# Rocketometer9DS1_2.net
KiCad netlist of a schematic drawn in EAGLE
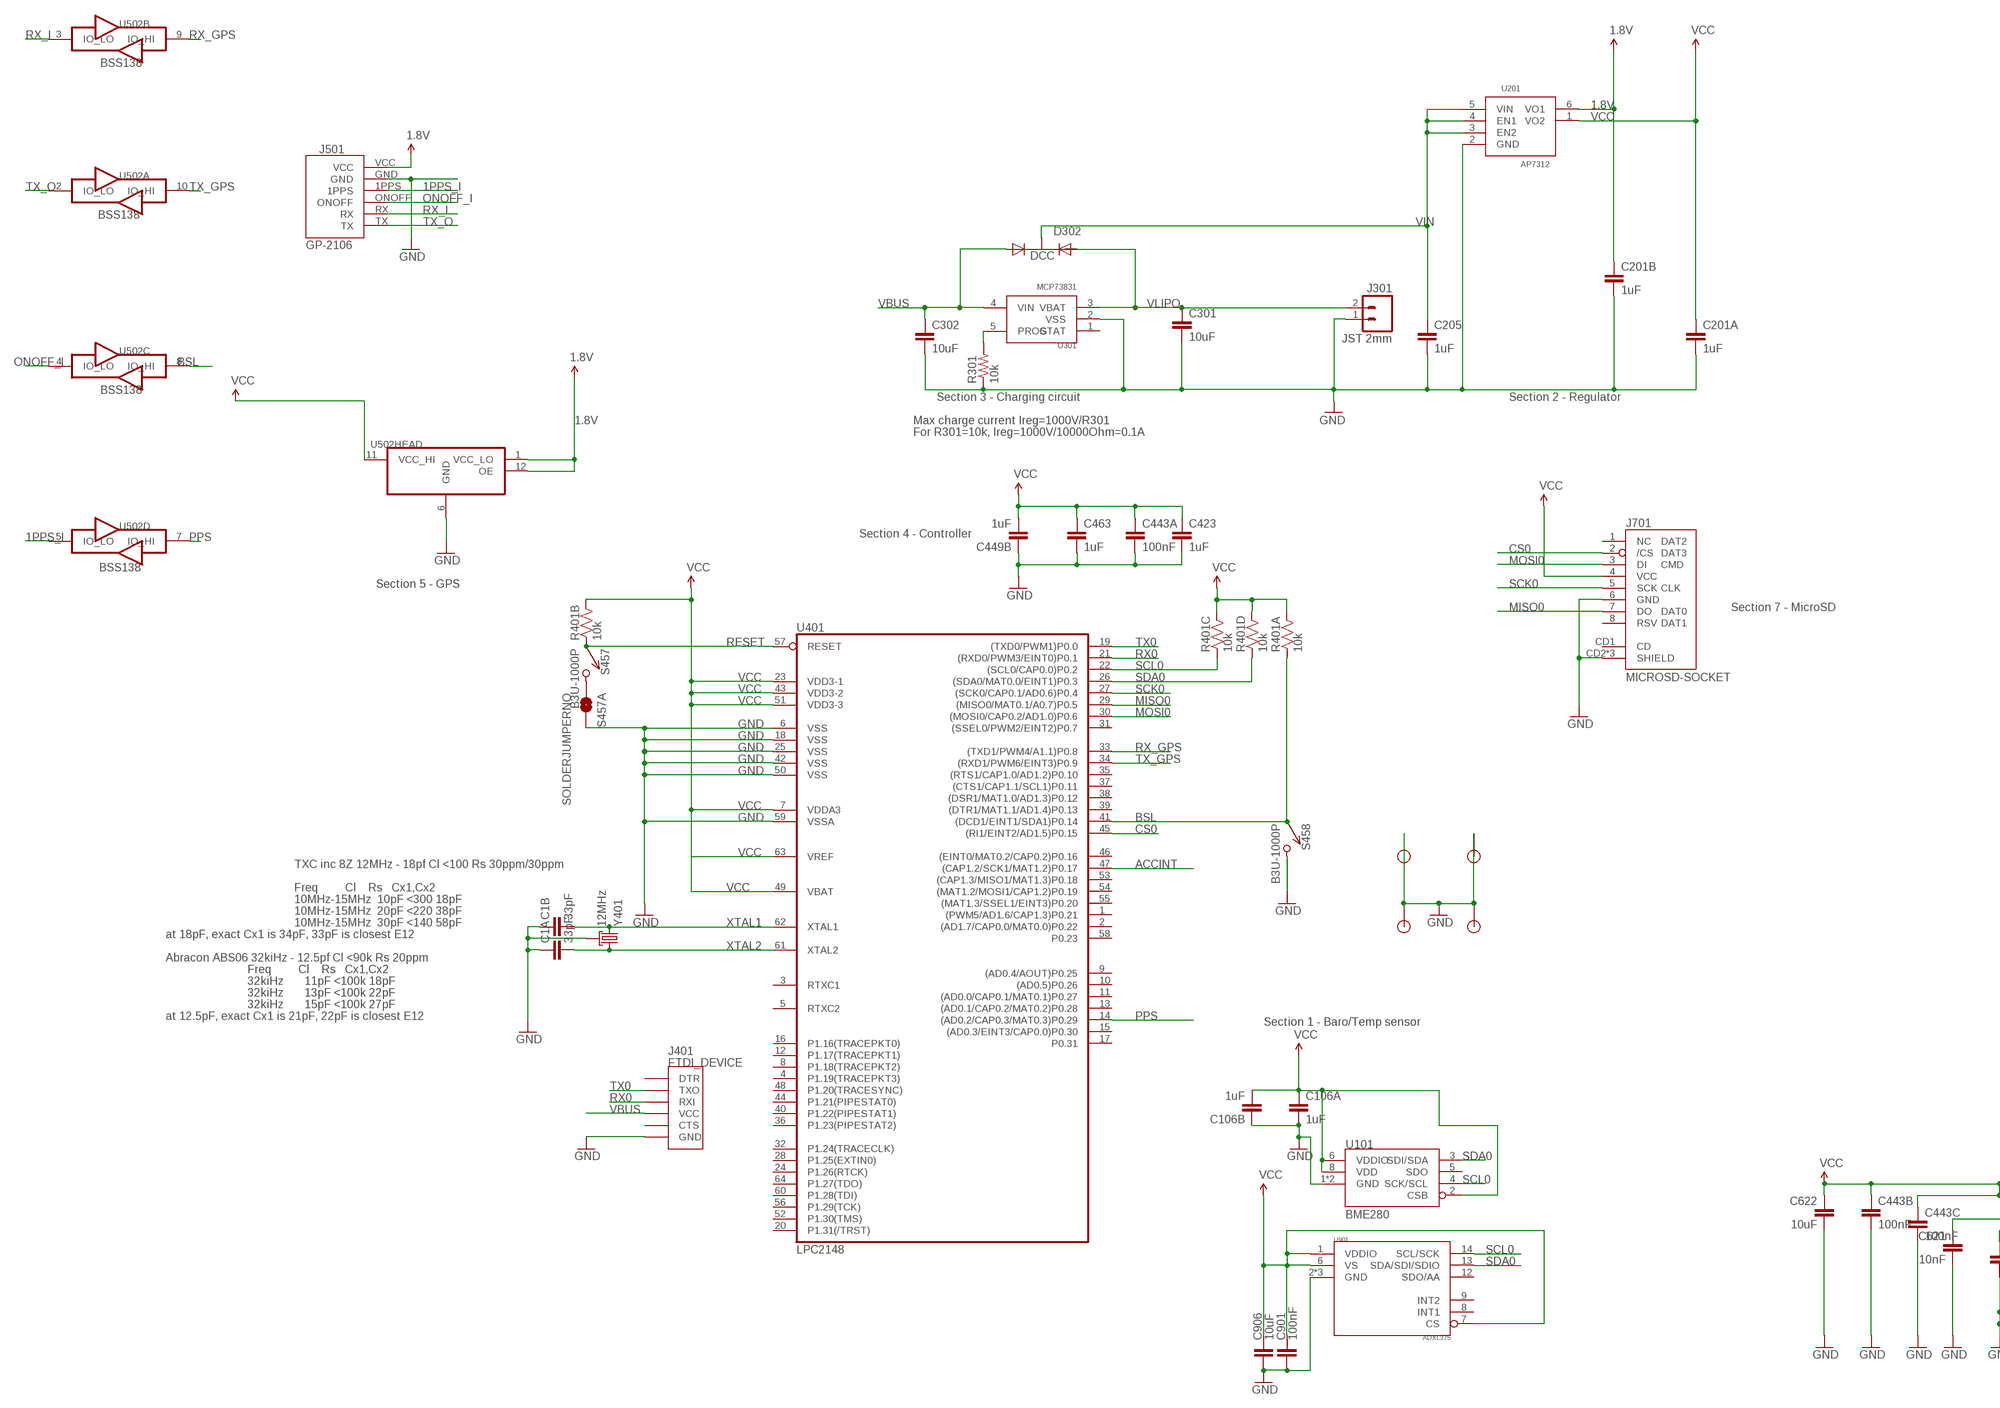
[diagram p0: schematic, sheet 1, part 1 of 2]
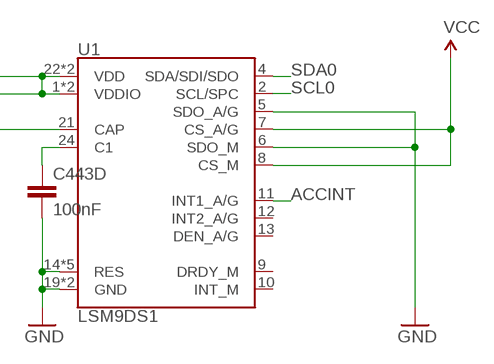
[diagram p1: schematic, sheet 1, part 2 of 2]

(export (version "E")
  (design (tool "Eeschema 10.0.6"))
  (components
    (comp (ref "C1")
      (value "33pF")
      (footprint "eagle-import:CKCM25")
      (libsource (lib "eagle-import") (part "CKCM25"))
    )
    (comp (ref "C106")
      (value "1uF")
      (footprint "eagle-import:CKCM25")
      (libsource (lib "eagle-import") (part "CKCM25"))
    )
    (comp (ref "C201")
      (value "1uF")
      (footprint "eagle-import:CKCM25")
      (libsource (lib "eagle-import") (part "CKCM25"))
    )
    (comp (ref "C205")
      (value "1uF")
      (footprint "eagle-import:0402-CAP")
      (libsource (lib "eagle-import") (part "CAP0402-CAP"))
    )
    (comp (ref "C301")
      (value "10uF")
      (footprint "eagle-import:0402-CAP")
      (libsource (lib "eagle-import") (part "CAP0402-CAP"))
    )
    (comp (ref "C302")
      (value "10uF")
      (footprint "eagle-import:0402-CAP")
      (libsource (lib "eagle-import") (part "CAP0402-CAP"))
    )
    (comp (ref "C423")
      (value "1uF")
      (footprint "eagle-import:0402-CAP")
      (libsource (lib "eagle-import") (part "CAP0402-CAP"))
    )
    (comp (ref "C443")
      (value "100nF")
      (footprint "eagle-import:CKCL44")
      (libsource (lib "eagle-import") (part "CKCX4L"))
    )
    (comp (ref "C449")
      (value "1uF")
      (footprint "eagle-import:CKCM25")
      (libsource (lib "eagle-import") (part "CKCM25"))
    )
    (comp (ref "C463")
      (value "1uF")
      (footprint "eagle-import:0402-CAP")
      (libsource (lib "eagle-import") (part "CAP0402-CAP"))
    )
    (comp (ref "C621")
      (value "10nF")
      (footprint "eagle-import:0402-CAP")
      (libsource (lib "eagle-import") (part "SparkFun-Capacitors_CAP0402-CAP"))
    )
    (comp (ref "C622")
      (value "10uF")
      (footprint "eagle-import:0402-CAP")
      (libsource (lib "eagle-import") (part "SparkFun-Capacitors_CAP0402-CAP"))
    )
    (comp (ref "C901")
      (value "100nF")
      (footprint "eagle-import:0402-CAP")
      (libsource (lib "eagle-import") (part "SparkFun-Passives_CAP0402-CAP"))
    )
    (comp (ref "C906")
      (value "10uF")
      (footprint "eagle-import:0402-CAP")
      (libsource (lib "eagle-import") (part "SparkFun-Capacitors_CAP0402-CAP"))
    )
    (comp (ref "D302")
      (value "DCC")
      (footprint "eagle-import:SOT-23-3")
      (libsource (lib "eagle-import") (part "PMEG2005CT"))
    )
    (comp (ref "J301")
      (value "JST 2mm")
      (footprint "eagle-import:1X02_NO_SILK")
      (libsource (lib "eagle-import") (part "M021X02_NO_SILK"))
    )
    (comp (ref "J401")
      (value "FTDI_DEVICE")
      (footprint "eagle-import:FTDI_DEVICE_SIDE")
      (libsource (lib "eagle-import") (part "FTDI_DEVICE"))
    )
    (comp (ref "J501")
      (value "GP-2106")
      (footprint "eagle-import:GP-2106")
      (libsource (lib "eagle-import") (part "GP-2106"))
    )
    (comp (ref "J701")
      (value "MICROSD-SOCKET")
      (footprint "eagle-import:MICROSD-SOCKET-PP")
      (libsource (lib "eagle-import") (part "MICROSD-SOCKET"))
    )
    (comp (ref "JP1")
      (value "STANDOFF")
      (footprint "eagle-import:STANDOFF")
      (libsource (lib "eagle-import") (part "STANDOFF"))
    )
    (comp (ref "JP2")
      (value "STANDOFF")
      (footprint "eagle-import:STANDOFF")
      (libsource (lib "eagle-import") (part "STANDOFF"))
    )
    (comp (ref "JP4")
      (value "STANDOFF")
      (footprint "eagle-import:STANDOFF")
      (libsource (lib "eagle-import") (part "STANDOFF"))
    )
    (comp (ref "JP5")
      (value "STANDOFF")
      (footprint "eagle-import:STANDOFF")
      (libsource (lib "eagle-import") (part "STANDOFF"))
    )
    (comp (ref "R301")
      (value "10k")
      (footprint "eagle-import:0402-RES")
      (libsource (lib "eagle-import") (part "RESISTOR0402-RES"))
    )
    (comp (ref "R401")
      (value "10k")
      (footprint "eagle-import:CRA04")
      (fields (field (name "DIGIKEY") "CRA4S810KCT-ND"))
      (libsource (lib "eagle-import") (part "RP404"))
    )
    (comp (ref "S457")
      (value "B3U-1000P")
      (footprint "eagle-import:B3U-1000P")
      (libsource (lib "eagle-import") (part "B3U-1000P"))
    )
    (comp (ref "S457A")
      (value "SOLDERJUMPERNO")
      (footprint "eagle-import:SJ_2S-NO")
      (libsource (lib "eagle-import") (part "SOLDERJUMPERNO"))
    )
    (comp (ref "S458")
      (value "B3U-1000P")
      (footprint "eagle-import:B3U-1000P")
      (libsource (lib "eagle-import") (part "B3U-1000P"))
    )
    (comp (ref "U1")
      (value "LSM9DS1")
      (footprint "eagle-import:LGA24-8X4")
      (libsource (lib "eagle-import") (part "LSM9DS1"))
    )
    (comp (ref "U101")
      (value "BME280")
      (footprint "eagle-import:BME280")
      (libsource (lib "eagle-import") (part "BME280"))
    )
    (comp (ref "U201")
      (value "AP7312")
      (footprint "eagle-import:SOT-23-6")
      (libsource (lib "eagle-import") (part "AP73X2"))
    )
    (comp (ref "U301")
      (value "MCP73831")
      (footprint "eagle-import:SOT-23-5")
      (libsource (lib "eagle-import") (part "MCP73831"))
    )
    (comp (ref "U401")
      (value "LPC2148")
      (footprint "eagle-import:SQFP-S-10X10-64")
      (libsource (lib "eagle-import") (part "LPC213X"))
    )
    (comp (ref "U502")
      (value "TXB0104RUT")
      (footprint "eagle-import:R-PUQFN-N12")
      (libsource (lib "eagle-import") (part "TXB0104RUT"))
    )
    (comp (ref "U901")
      (value "ADXL375")
      (footprint "eagle-import:ADXL375")
      (libsource (lib "eagle-import") (part "ADXL375"))
    )
    (comp (ref "Y401")
      (value "12MHz")
      (footprint "eagle-import:CRYSTAL_SMD_2MM_2_5MM")
      (libsource (lib "eagle-import") (part "CX2520"))
    )
  )
  (nets
    (net (code "1") (name "/1PPS_I") (class "Default")
      (node (ref "J501") (pin "1PPS") (pinfunction "1PPS_1PPS") (pintype "bidirectional"))
      (node (ref "U502") (pin "5") (pinfunction "IO_LO_5") (pintype "bidirectional"))
    )
    (net (code "2") (name "/ACCINT") (class "Default")
      (node (ref "U1") (pin "11") (pinfunction "INT1_A/G_11") (pintype "bidirectional"))
      (node (ref "U401") (pin "47") (pinfunction "(CAP1.2/SCK1/MAT1.2)P0.17_47") (pintype "bidirectional"))
    )
    (net (code "3") (name "/BSL") (class "Default")
      (node (ref "R401") (pin "1") (pinfunction "1_1") (pintype "passive"))
      (node (ref "S458") (pin "P$1") (pinfunction "1_P$1") (pintype "bidirectional"))
      (node (ref "U401") (pin "41") (pinfunction "(DCD1/EINT1/SDA1)P0.14_41") (pintype "bidirectional"))
      (node (ref "U502") (pin "8") (pinfunction "IO_HI_8") (pintype "bidirectional"))
    )
    (net (code "4") (name "/CS0") (class "Default")
      (node (ref "J701") (pin "2") (pinfunction "/CS_2") (pintype "bidirectional"))
      (node (ref "U401") (pin "45") (pinfunction "(RI1/EINT2/AD1.5)P0.15_45") (pintype "bidirectional"))
    )
    (net (code "5") (name "/MISO0") (class "Default")
      (node (ref "J701") (pin "7") (pinfunction "DO_7") (pintype "bidirectional"))
      (node (ref "U401") (pin "29") (pinfunction "(MISO0/MAT0.1/A0.7)P0.5_29") (pintype "bidirectional"))
    )
    (net (code "6") (name "/MOSI0") (class "Default")
      (node (ref "J701") (pin "3") (pinfunction "DI_3") (pintype "bidirectional"))
      (node (ref "U401") (pin "30") (pinfunction "(MOSI0/CAP0.2/AD1.0)P0.6_30") (pintype "bidirectional"))
    )
    (net (code "7") (name "/ONOFF_I") (class "Default")
      (node (ref "J501") (pin "ONOFF") (pinfunction "ONOFF_ONOFF") (pintype "bidirectional"))
      (node (ref "U502") (pin "4") (pinfunction "IO_LO_4") (pintype "bidirectional"))
    )
    (net (code "8") (name "/PPS") (class "Default")
      (node (ref "U401") (pin "14") (pinfunction "(AD0.2/CAP0.3/MAT0.3)P0.29_14") (pintype "bidirectional"))
      (node (ref "U502") (pin "7") (pinfunction "IO_HI_7") (pintype "bidirectional"))
    )
    (net (code "9") (name "/RESET") (class "Default")
      (node (ref "R401") (pin "2") (pinfunction "1_2") (pintype "passive"))
      (node (ref "S457") (pin "P$1") (pinfunction "1_P$1") (pintype "bidirectional"))
      (node (ref "U401") (pin "57") (pinfunction "RESET_57") (pintype "input"))
    )
    (net (code "10") (name "/RX0") (class "Default")
      (node (ref "J401") (pin "P$3") (pinfunction "RXI_P$3") (pintype "bidirectional"))
      (node (ref "U401") (pin "21") (pinfunction "(RXD0/PWM3/EINT0)P0.1_21") (pintype "bidirectional"))
    )
    (net (code "11") (name "/RX_GPS") (class "Default")
      (node (ref "U401") (pin "33") (pinfunction "(TXD1/PWM4/A1.1)P0.8_33") (pintype "bidirectional"))
      (node (ref "U502") (pin "9") (pinfunction "IO_HI_9") (pintype "bidirectional"))
    )
    (net (code "12") (name "/RX_I") (class "Default")
      (node (ref "J501") (pin "RX") (pinfunction "RX_RX") (pintype "bidirectional"))
      (node (ref "U502") (pin "3") (pinfunction "IO_LO_3") (pintype "bidirectional"))
    )
    (net (code "13") (name "/SCK0") (class "Default")
      (node (ref "J701") (pin "5") (pinfunction "SCK_5") (pintype "bidirectional"))
      (node (ref "U401") (pin "27") (pinfunction "(SCK0/CAP0.1/AD0.6)P0.4_27") (pintype "bidirectional"))
    )
    (net (code "14") (name "/SCL0") (class "Default")
      (node (ref "R401") (pin "3") (pinfunction "1_3") (pintype "passive"))
      (node (ref "U1") (pin "2") (pinfunction "SCL/SPC_2") (pintype "bidirectional"))
      (node (ref "U101") (pin "4") (pinfunction "SCK/SCL_4") (pintype "input"))
      (node (ref "U401") (pin "22") (pinfunction "(SCL0/CAP0.0)P0.2_22") (pintype "bidirectional"))
      (node (ref "U901") (pin "14") (pinfunction "SCL/SCK_14") (pintype "input"))
    )
    (net (code "15") (name "/SDA0") (class "Default")
      (node (ref "R401") (pin "4") (pinfunction "1_4") (pintype "passive"))
      (node (ref "U1") (pin "4") (pinfunction "SDA/SDI/SDO_4") (pintype "bidirectional"))
      (node (ref "U101") (pin "3") (pinfunction "SDI/SDA_3") (pintype "bidirectional"))
      (node (ref "U401") (pin "26") (pinfunction "(SDA0/MAT0.0/EINT1)P0.3_26") (pintype "bidirectional"))
      (node (ref "U901") (pin "13") (pinfunction "SDA/SDI/SDIO_13") (pintype "bidirectional"))
    )
    (net (code "16") (name "/TX0") (class "Default")
      (node (ref "J401") (pin "P$2") (pinfunction "TXO_P$2") (pintype "bidirectional"))
      (node (ref "U401") (pin "19") (pinfunction "(TXD0/PWM1)P0.0_19") (pintype "bidirectional"))
    )
    (net (code "17") (name "/TX_GPS") (class "Default")
      (node (ref "U401") (pin "34") (pinfunction "(RXD1/PWM6/EINT3)P0.9_34") (pintype "bidirectional"))
      (node (ref "U502") (pin "10") (pinfunction "IO_HI_10") (pintype "bidirectional"))
    )
    (net (code "18") (name "/TX_O") (class "Default")
      (node (ref "J501") (pin "TX") (pinfunction "TX_TX") (pintype "bidirectional"))
      (node (ref "U502") (pin "2") (pinfunction "IO_LO_2") (pintype "bidirectional"))
    )
    (net (code "19") (name "/VBUS") (class "Default")
      (node (ref "C302") (pin "1") (pinfunction "1_1") (pintype "passive"))
      (node (ref "D302") (pin "1") (pinfunction "A1_1") (pintype "passive"))
      (node (ref "J401") (pin "P$4") (pinfunction "VCC_P$4") (pintype "bidirectional"))
      (node (ref "U301") (pin "4") (pinfunction "VIN_4") (pintype "power_in"))
    )
    (net (code "20") (name "/VIN") (class "Default")
      (node (ref "C205") (pin "1") (pinfunction "1_1") (pintype "passive"))
      (node (ref "D302") (pin "3") (pinfunction "K_3") (pintype "passive"))
      (node (ref "U201") (pin "3") (pinfunction "EN2_3") (pintype "bidirectional"))
      (node (ref "U201") (pin "4") (pinfunction "EN1_4") (pintype "bidirectional"))
      (node (ref "U201") (pin "5") (pinfunction "VIN_5") (pintype "bidirectional"))
    )
    (net (code "21") (name "/VLIPO") (class "Default")
      (node (ref "C301") (pin "1") (pinfunction "1_1") (pintype "passive"))
      (node (ref "D302") (pin "2") (pinfunction "A2_2") (pintype "passive"))
      (node (ref "J301") (pin "2") (pinfunction "2_2") (pintype "passive"))
      (node (ref "U301") (pin "3") (pinfunction "VBAT_3") (pintype "power_in"))
    )
    (net (code "22") (name "/XTAL1") (class "Default")
      (node (ref "C1") (pin "3") (pinfunction "2_3") (pintype "passive"))
      (node (ref "U401") (pin "62") (pinfunction "XTAL1_62") (pintype "input"))
      (node (ref "Y401") (pin "3") (pinfunction "2_3") (pintype "passive"))
    )
    (net (code "23") (name "/XTAL2") (class "Default")
      (node (ref "C1") (pin "4") (pinfunction "2_4") (pintype "passive"))
      (node (ref "U401") (pin "61") (pinfunction "XTAL2_61") (pintype "output"))
      (node (ref "Y401") (pin "1") (pinfunction "1_1") (pintype "passive"))
    )
    (net (code "24") (name "1.8V") (class "Default")
      (node (ref "C201") (pin "2") (pinfunction "1_2") (pintype "passive"))
      (node (ref "J501") (pin "VCC") (pinfunction "VCC_VCC") (pintype "bidirectional"))
      (node (ref "U201") (pin "6") (pinfunction "VO1_6") (pintype "bidirectional"))
      (node (ref "U502") (pin "1") (pinfunction "VCC_LO_1") (pintype "power_in"))
      (node (ref "U502") (pin "12") (pinfunction "OE_12") (pintype "bidirectional"))
    )
    (net (code "25") (name "GND") (class "Default")
      (node (ref "C1") (pin "1") (pinfunction "1_1") (pintype "passive"))
      (node (ref "C1") (pin "2") (pinfunction "1_2") (pintype "passive"))
      (node (ref "C106") (pin "2") (pinfunction "1_2") (pintype "passive"))
      (node (ref "C106") (pin "4") (pinfunction "2_4") (pintype "passive"))
      (node (ref "C201") (pin "3") (pinfunction "2_3") (pintype "passive"))
      (node (ref "C201") (pin "4") (pinfunction "2_4") (pintype "passive"))
      (node (ref "C205") (pin "2") (pinfunction "2_2") (pintype "passive"))
      (node (ref "C301") (pin "2") (pinfunction "2_2") (pintype "passive"))
      (node (ref "C302") (pin "2") (pinfunction "2_2") (pintype "passive"))
      (node (ref "C423") (pin "2") (pinfunction "2_2") (pintype "passive"))
      (node (ref "C443") (pin "5") (pinfunction "2_5") (pintype "passive"))
      (node (ref "C443") (pin "6") (pinfunction "2_6") (pintype "passive"))
      (node (ref "C443") (pin "7") (pinfunction "2_7") (pintype "passive"))
      (node (ref "C443") (pin "8") (pinfunction "2_8") (pintype "passive"))
      (node (ref "C449") (pin "2") (pinfunction "1_2") (pintype "passive"))
      (node (ref "C463") (pin "2") (pinfunction "2_2") (pintype "passive"))
      (node (ref "C621") (pin "2") (pinfunction "2_2") (pintype "passive"))
      (node (ref "C622") (pin "2") (pinfunction "2_2") (pintype "passive"))
      (node (ref "C901") (pin "2") (pinfunction "2_2") (pintype "passive"))
      (node (ref "C906") (pin "2") (pinfunction "2_2") (pintype "passive"))
      (node (ref "J301") (pin "1") (pinfunction "1_1") (pintype "passive"))
      (node (ref "J401") (pin "P$6") (pinfunction "GND_P$6") (pintype "bidirectional"))
      (node (ref "J501") (pin "GND") (pinfunction "GND_GND") (pintype "bidirectional"))
      (node (ref "J701") (pin "6") (pinfunction "GND_6") (pintype "bidirectional"))
      (node (ref "J701") (pin "CD2") (pinfunction "SHIELD_CD2") (pintype "bidirectional"))
      (node (ref "J701") (pin "GND1") (pinfunction "SHIELD_GND1") (pintype "bidirectional"))
      (node (ref "J701") (pin "GND3") (pinfunction "SHIELD_GND3") (pintype "bidirectional"))
      (node (ref "JP1") (pin "P$1") (pinfunction "P$1_P$1") (pintype "bidirectional"))
      (node (ref "JP2") (pin "P$1") (pinfunction "P$1_P$1") (pintype "bidirectional"))
      (node (ref "JP4") (pin "P$1") (pinfunction "P$1_P$1") (pintype "bidirectional"))
      (node (ref "JP5") (pin "P$1") (pinfunction "P$1_P$1") (pintype "bidirectional"))
      (node (ref "R301") (pin "1") (pinfunction "1_1") (pintype "passive"))
      (node (ref "S457A") (pin "2") (pinfunction "2_2") (pintype "passive"))
      (node (ref "S458") (pin "P$2") (pinfunction "2_P$2") (pintype "bidirectional"))
      (node (ref "U1") (pin "14") (pinfunction "RES_14") (pintype "bidirectional"))
      (node (ref "U1") (pin "15") (pinfunction "RES_15") (pintype "bidirectional"))
      (node (ref "U1") (pin "16") (pinfunction "RES_16") (pintype "bidirectional"))
      (node (ref "U1") (pin "17") (pinfunction "RES_17") (pintype "bidirectional"))
      (node (ref "U1") (pin "18") (pinfunction "RES_18") (pintype "bidirectional"))
      (node (ref "U1") (pin "19") (pinfunction "GND_19") (pintype "bidirectional"))
      (node (ref "U1") (pin "20") (pinfunction "GND_20") (pintype "bidirectional"))
      (node (ref "U1") (pin "5") (pinfunction "SDO_A/G_5") (pintype "bidirectional"))
      (node (ref "U1") (pin "6") (pinfunction "SDO_M_6") (pintype "bidirectional"))
      (node (ref "U101") (pin "1") (pinfunction "GND_1") (pintype "power_in"))
      (node (ref "U101") (pin "7") (pinfunction "GND_7") (pintype "power_in"))
      (node (ref "U201") (pin "2") (pinfunction "GND_2") (pintype "bidirectional"))
      (node (ref "U301") (pin "2") (pinfunction "VSS_2") (pintype "power_in"))
      (node (ref "U401") (pin "18") (pinfunction "VSS_18") (pintype "power_in"))
      (node (ref "U401") (pin "25") (pinfunction "VSS_25") (pintype "power_in"))
      (node (ref "U401") (pin "42") (pinfunction "VSS_42") (pintype "power_in"))
      (node (ref "U401") (pin "50") (pinfunction "VSS_50") (pintype "power_in"))
      (node (ref "U401") (pin "59") (pinfunction "VSSA_59") (pintype "power_in"))
      (node (ref "U401") (pin "6") (pinfunction "VSS_6") (pintype "power_in"))
      (node (ref "U502") (pin "6") (pinfunction "GND_6") (pintype "power_in"))
      (node (ref "U901") (pin "2") (pinfunction "GND_2") (pintype "power_in"))
      (node (ref "U901") (pin "4") (pinfunction "GND_4") (pintype "power_in"))
      (node (ref "U901") (pin "5") (pinfunction "GND_5") (pintype "power_in"))
      (node (ref "Y401") (pin "2") (pinfunction "GND_2") (pintype "passive"))
      (node (ref "Y401") (pin "4") (pinfunction "GND_4") (pintype "passive"))
    )
    (net (code "26") (name "Net-(C443D-1)") (class "Default")
      (node (ref "C443") (pin "4") (pinfunction "1_4") (pintype "passive"))
      (node (ref "U1") (pin "24") (pinfunction "C1_24") (pintype "bidirectional"))
    )
    (net (code "27") (name "Net-(S457-2)") (class "Default")
      (node (ref "S457") (pin "P$2") (pinfunction "2_P$2") (pintype "bidirectional"))
      (node (ref "S457A") (pin "1") (pinfunction "1_1") (pintype "passive"))
    )
    (net (code "28") (name "Net-(U1-CAP)") (class "Default")
      (node (ref "C621") (pin "1") (pinfunction "1_1") (pintype "passive"))
      (node (ref "U1") (pin "21") (pinfunction "CAP_21") (pintype "bidirectional"))
    )
    (net (code "29") (name "Net-(U301-PROG)") (class "Default")
      (node (ref "R301") (pin "2") (pinfunction "2_2") (pintype "passive"))
      (node (ref "U301") (pin "5") (pinfunction "PROG_5") (pintype "passive"))
    )
    (net (code "30") (name "VCC") (class "Default")
      (node (ref "C106") (pin "1") (pinfunction "1_1") (pintype "passive"))
      (node (ref "C106") (pin "3") (pinfunction "2_3") (pintype "passive"))
      (node (ref "C201") (pin "1") (pinfunction "1_1") (pintype "passive"))
      (node (ref "C423") (pin "1") (pinfunction "1_1") (pintype "passive"))
      (node (ref "C443") (pin "1") (pinfunction "1_1") (pintype "passive"))
      (node (ref "C443") (pin "2") (pinfunction "1_2") (pintype "passive"))
      (node (ref "C443") (pin "3") (pinfunction "1_3") (pintype "passive"))
      (node (ref "C449") (pin "3") (pinfunction "2_3") (pintype "passive"))
      (node (ref "C463") (pin "1") (pinfunction "1_1") (pintype "passive"))
      (node (ref "C622") (pin "1") (pinfunction "1_1") (pintype "passive"))
      (node (ref "C901") (pin "1") (pinfunction "1_1") (pintype "passive"))
      (node (ref "C906") (pin "1") (pinfunction "1_1") (pintype "passive"))
      (node (ref "J701") (pin "4") (pinfunction "VCC_4") (pintype "bidirectional"))
      (node (ref "R401") (pin "5") (pinfunction "2_5") (pintype "passive"))
      (node (ref "R401") (pin "6") (pinfunction "2_6") (pintype "passive"))
      (node (ref "R401") (pin "7") (pinfunction "2_7") (pintype "passive"))
      (node (ref "R401") (pin "8") (pinfunction "2_8") (pintype "passive"))
      (node (ref "U1") (pin "1") (pinfunction "VDDIO_1") (pintype "bidirectional"))
      (node (ref "U1") (pin "22") (pinfunction "VDD_22") (pintype "bidirectional"))
      (node (ref "U1") (pin "23") (pinfunction "VDD_23") (pintype "bidirectional"))
      (node (ref "U1") (pin "3") (pinfunction "VDDIO_3") (pintype "bidirectional"))
      (node (ref "U1") (pin "7") (pinfunction "CS_A/G_7") (pintype "bidirectional"))
      (node (ref "U1") (pin "8") (pinfunction "CS_M_8") (pintype "bidirectional"))
      (node (ref "U101") (pin "2") (pinfunction "CSB_2") (pintype "input"))
      (node (ref "U101") (pin "6") (pinfunction "VDDIO_6") (pintype "power_in"))
      (node (ref "U101") (pin "8") (pinfunction "VDD_8") (pintype "power_in"))
      (node (ref "U201") (pin "1") (pinfunction "VO2_1") (pintype "bidirectional"))
      (node (ref "U401") (pin "23") (pinfunction "VDD3-1_23") (pintype "power_in"))
      (node (ref "U401") (pin "43") (pinfunction "VDD3-2_43") (pintype "power_in"))
      (node (ref "U401") (pin "49") (pinfunction "VBAT_49") (pintype "power_in"))
      (node (ref "U401") (pin "51") (pinfunction "VDD3-3_51") (pintype "power_in"))
      (node (ref "U401") (pin "63") (pinfunction "VREF_63") (pintype "input"))
      (node (ref "U401") (pin "7") (pinfunction "VDDA3_7") (pintype "power_in"))
      (node (ref "U502") (pin "11") (pinfunction "VCC_HI_11") (pintype "power_in"))
      (node (ref "U901") (pin "1") (pinfunction "VDDIO_1") (pintype "power_in"))
      (node (ref "U901") (pin "6") (pinfunction "VS_6") (pintype "power_in"))
      (node (ref "U901") (pin "7") (pinfunction "CS_7") (pintype "input"))
    )
    (net (code "31") (name "unconnected-(J401-CTS-PadP$5)") (class "Default")
      (node (ref "J401") (pin "P$5") (pinfunction "CTS_P$5") (pintype "bidirectional"))
    )
    (net (code "32") (name "unconnected-(J401-DTR-PadP$1)") (class "Default")
      (node (ref "J401") (pin "P$1") (pinfunction "DTR_P$1") (pintype "bidirectional"))
    )
    (net (code "33") (name "unconnected-(J701-CD-PadCD1)") (class "Default")
      (node (ref "J701") (pin "CD1") (pinfunction "CD_CD1") (pintype "bidirectional"))
    )
    (net (code "34") (name "unconnected-(J701-NC-Pad1)") (class "Default")
      (node (ref "J701") (pin "1") (pinfunction "NC_1") (pintype "bidirectional"))
    )
    (net (code "35") (name "unconnected-(J701-RSV-Pad8)") (class "Default")
      (node (ref "J701") (pin "8") (pinfunction "RSV_8") (pintype "bidirectional"))
    )
    (net (code "36") (name "unconnected-(U1-DEN_A{slash}G-Pad13)") (class "Default")
      (node (ref "U1") (pin "13") (pinfunction "DEN_A/G_13") (pintype "bidirectional"))
    )
    (net (code "37") (name "unconnected-(U1-DRDY_M-Pad9)") (class "Default")
      (node (ref "U1") (pin "9") (pinfunction "DRDY_M_9") (pintype "bidirectional"))
    )
    (net (code "38") (name "unconnected-(U1-INT2_A{slash}G-Pad12)") (class "Default")
      (node (ref "U1") (pin "12") (pinfunction "INT2_A/G_12") (pintype "bidirectional"))
    )
    (net (code "39") (name "unconnected-(U1-INT_M-Pad10)") (class "Default")
      (node (ref "U1") (pin "10") (pinfunction "INT_M_10") (pintype "bidirectional"))
    )
    (net (code "40") (name "unconnected-(U101-SDO-Pad5)") (class "Default")
      (node (ref "U101") (pin "5") (pinfunction "SDO_5") (pintype "bidirectional"))
    )
    (net (code "41") (name "unconnected-(U301-STAT-Pad1)") (class "Default")
      (node (ref "U301") (pin "1") (pinfunction "STAT_1") (pintype "bidirectional"))
    )
    (net (code "42") (name "unconnected-(U401-(AD0.0{slash}CAP0.1{slash}MAT0.1)P0.27-Pad11)") (class "Default")
      (node (ref "U401") (pin "11") (pinfunction "(AD0.0/CAP0.1/MAT0.1)P0.27_11") (pintype "bidirectional"))
    )
    (net (code "43") (name "unconnected-(U401-(AD0.1{slash}CAP0.2{slash}MAT0.2)P0.28-Pad13)") (class "Default")
      (node (ref "U401") (pin "13") (pinfunction "(AD0.1/CAP0.2/MAT0.2)P0.28_13") (pintype "bidirectional"))
    )
    (net (code "44") (name "unconnected-(U401-(AD0.3{slash}EINT3{slash}CAP0.0)P0.30-Pad15)") (class "Default")
      (node (ref "U401") (pin "15") (pinfunction "(AD0.3/EINT3/CAP0.0)P0.30_15") (pintype "bidirectional"))
    )
    (net (code "45") (name "unconnected-(U401-(AD0.4{slash}AOUT)P0.25-Pad9)") (class "Default")
      (node (ref "U401") (pin "9") (pinfunction "(AD0.4/AOUT)P0.25_9") (pintype "bidirectional"))
    )
    (net (code "46") (name "unconnected-(U401-(AD0.5)P0.26-Pad10)") (class "Default")
      (node (ref "U401") (pin "10") (pinfunction "(AD0.5)P0.26_10") (pintype "bidirectional"))
    )
    (net (code "47") (name "unconnected-(U401-(AD1.7{slash}CAP0.0{slash}MAT0.0)P0.22-Pad2)") (class "Default")
      (node (ref "U401") (pin "2") (pinfunction "(AD1.7/CAP0.0/MAT0.0)P0.22_2") (pintype "bidirectional"))
    )
    (net (code "48") (name "unconnected-(U401-(CAP1.3{slash}MISO1{slash}MAT1.3)P0.18-Pad53)") (class "Default")
      (node (ref "U401") (pin "53") (pinfunction "(CAP1.3/MISO1/MAT1.3)P0.18_53") (pintype "bidirectional"))
    )
    (net (code "49") (name "unconnected-(U401-(CTS1{slash}CAP1.1{slash}SCL1)P0.11-Pad37)") (class "Default")
      (node (ref "U401") (pin "37") (pinfunction "(CTS1/CAP1.1/SCL1)P0.11_37") (pintype "bidirectional"))
    )
    (net (code "50") (name "unconnected-(U401-(DSR1{slash}MAT1.0{slash}AD1.3)P0.12-Pad38)") (class "Default")
      (node (ref "U401") (pin "38") (pinfunction "(DSR1/MAT1.0/AD1.3)P0.12_38") (pintype "bidirectional"))
    )
    (net (code "51") (name "unconnected-(U401-(DTR1{slash}MAT1.1{slash}AD1.4)P0.13-Pad39)") (class "Default")
      (node (ref "U401") (pin "39") (pinfunction "(DTR1/MAT1.1/AD1.4)P0.13_39") (pintype "bidirectional"))
    )
    (net (code "52") (name "unconnected-(U401-(EINT0{slash}MAT0.2{slash}CAP0.2)P0.16-Pad46)") (class "Default")
      (node (ref "U401") (pin "46") (pinfunction "(EINT0/MAT0.2/CAP0.2)P0.16_46") (pintype "bidirectional"))
    )
    (net (code "53") (name "unconnected-(U401-(MAT1.2{slash}MOSI1{slash}CAP1.2)P0.19-Pad54)") (class "Default")
      (node (ref "U401") (pin "54") (pinfunction "(MAT1.2/MOSI1/CAP1.2)P0.19_54") (pintype "bidirectional"))
    )
    (net (code "54") (name "unconnected-(U401-(MAT1.3{slash}SSEL1{slash}EINT3)P0.20-Pad55)") (class "Default")
      (node (ref "U401") (pin "55") (pinfunction "(MAT1.3/SSEL1/EINT3)P0.20_55") (pintype "bidirectional"))
    )
    (net (code "55") (name "unconnected-(U401-(PWM5{slash}AD1.6{slash}CAP1.3)P0.21-Pad1)") (class "Default")
      (node (ref "U401") (pin "1") (pinfunction "(PWM5/AD1.6/CAP1.3)P0.21_1") (pintype "bidirectional"))
    )
    (net (code "56") (name "unconnected-(U401-(RTS1{slash}CAP1.0{slash}AD1.2)P0.10-Pad35)") (class "Default")
      (node (ref "U401") (pin "35") (pinfunction "(RTS1/CAP1.0/AD1.2)P0.10_35") (pintype "bidirectional"))
    )
    (net (code "57") (name "unconnected-(U401-(SSEL0{slash}PWM2{slash}EINT2)P0.7-Pad31)") (class "Default")
      (node (ref "U401") (pin "31") (pinfunction "(SSEL0/PWM2/EINT2)P0.7_31") (pintype "bidirectional"))
    )
    (net (code "58") (name "unconnected-(U401-P0.23-Pad58)") (class "Default")
      (node (ref "U401") (pin "58") (pinfunction "P0.23_58") (pintype "bidirectional"))
    )
    (net (code "59") (name "unconnected-(U401-P0.31-Pad17)") (class "Default")
      (node (ref "U401") (pin "17") (pinfunction "P0.31_17") (pintype "output"))
    )
    (net (code "60") (name "unconnected-(U401-P1.16(TRACEPKT0)-Pad16)") (class "Default")
      (node (ref "U401") (pin "16") (pinfunction "P1.16(TRACEPKT0)_16") (pintype "bidirectional"))
    )
    (net (code "61") (name "unconnected-(U401-P1.17(TRACEPKT1)-Pad12)") (class "Default")
      (node (ref "U401") (pin "12") (pinfunction "P1.17(TRACEPKT1)_12") (pintype "bidirectional"))
    )
    (net (code "62") (name "unconnected-(U401-P1.18(TRACEPKT2)-Pad8)") (class "Default")
      (node (ref "U401") (pin "8") (pinfunction "P1.18(TRACEPKT2)_8") (pintype "bidirectional"))
    )
    (net (code "63") (name "unconnected-(U401-P1.19(TRACEPKT3)-Pad4)") (class "Default")
      (node (ref "U401") (pin "4") (pinfunction "P1.19(TRACEPKT3)_4") (pintype "bidirectional"))
    )
    (net (code "64") (name "unconnected-(U401-P1.20(TRACESYNC)-Pad48)") (class "Default")
      (node (ref "U401") (pin "48") (pinfunction "P1.20(TRACESYNC)_48") (pintype "bidirectional"))
    )
    (net (code "65") (name "unconnected-(U401-P1.21(PIPESTAT0)-Pad44)") (class "Default")
      (node (ref "U401") (pin "44") (pinfunction "P1.21(PIPESTAT0)_44") (pintype "bidirectional"))
    )
    (net (code "66") (name "unconnected-(U401-P1.22(PIPESTAT1)-Pad40)") (class "Default")
      (node (ref "U401") (pin "40") (pinfunction "P1.22(PIPESTAT1)_40") (pintype "bidirectional"))
    )
    (net (code "67") (name "unconnected-(U401-P1.23(PIPESTAT2)-Pad36)") (class "Default")
      (node (ref "U401") (pin "36") (pinfunction "P1.23(PIPESTAT2)_36") (pintype "bidirectional"))
    )
    (net (code "68") (name "unconnected-(U401-P1.24(TRACECLK)-Pad32)") (class "Default")
      (node (ref "U401") (pin "32") (pinfunction "P1.24(TRACECLK)_32") (pintype "bidirectional"))
    )
    (net (code "69") (name "unconnected-(U401-P1.25(EXTIN0)-Pad28)") (class "Default")
      (node (ref "U401") (pin "28") (pinfunction "P1.25(EXTIN0)_28") (pintype "bidirectional"))
    )
    (net (code "70") (name "unconnected-(U401-P1.26(RTCK)-Pad24)") (class "Default")
      (node (ref "U401") (pin "24") (pinfunction "P1.26(RTCK)_24") (pintype "bidirectional"))
    )
    (net (code "71") (name "unconnected-(U401-P1.27(TDO)-Pad64)") (class "Default")
      (node (ref "U401") (pin "64") (pinfunction "P1.27(TDO)_64") (pintype "bidirectional"))
    )
    (net (code "72") (name "unconnected-(U401-P1.28(TDI)-Pad60)") (class "Default")
      (node (ref "U401") (pin "60") (pinfunction "P1.28(TDI)_60") (pintype "bidirectional"))
    )
    (net (code "73") (name "unconnected-(U401-P1.29(TCK)-Pad56)") (class "Default")
      (node (ref "U401") (pin "56") (pinfunction "P1.29(TCK)_56") (pintype "bidirectional"))
    )
    (net (code "74") (name "unconnected-(U401-P1.30(TMS)-Pad52)") (class "Default")
      (node (ref "U401") (pin "52") (pinfunction "P1.30(TMS)_52") (pintype "bidirectional"))
    )
    (net (code "75") (name "unconnected-(U401-P1.31({slash}TRST)-Pad20)") (class "Default")
      (node (ref "U401") (pin "20") (pinfunction "P1.31(/TRST)_20") (pintype "bidirectional"))
    )
    (net (code "76") (name "unconnected-(U401-RTXC1-Pad3)") (class "Default")
      (node (ref "U401") (pin "3") (pinfunction "RTXC1_3") (pintype "input"))
    )
    (net (code "77") (name "unconnected-(U401-RTXC2-Pad5)") (class "Default")
      (node (ref "U401") (pin "5") (pinfunction "RTXC2_5") (pintype "output"))
    )
    (net (code "78") (name "unconnected-(U901-INT1-Pad8)") (class "Default")
      (node (ref "U901") (pin "8") (pinfunction "INT1_8") (pintype "output"))
    )
    (net (code "79") (name "unconnected-(U901-INT2-Pad9)") (class "Default")
      (node (ref "U901") (pin "9") (pinfunction "INT2_9") (pintype "output"))
    )
    (net (code "80") (name "unconnected-(U901-SDO{slash}AA-Pad12)") (class "Default")
      (node (ref "U901") (pin "12") (pinfunction "SDO/AA_12") (pintype "bidirectional"))
    )
  )
)
